# display.net
KiCad netlist of a schematic drawn in Altium Designer
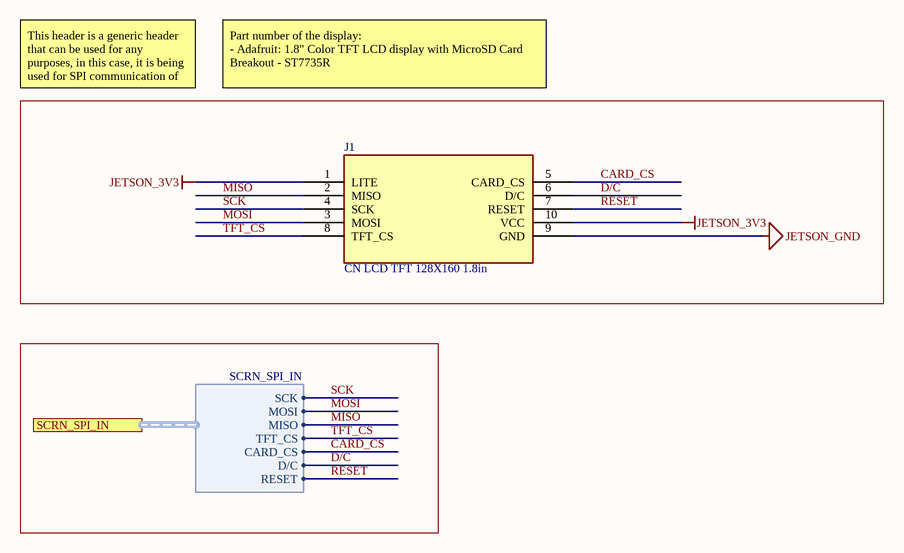
[diagram p0: display.SchDoc]

(export (version "E")
  (design (tool "Eeschema 10.0.6"))
  (components
    (comp (ref "J1")
      (value "CN LCD TFT 128X160 1.8in")
      (footprint "CN LCD TFT 128X160 1.8in")
      (libsource (lib "Connector_Library") (part "CN LCD TFT 128X160 1.8in"))
    )
  )
  (nets
    (net (code "2") (name "/CARD_CS") (class "Default")
      (node (ref "J1") (pin "5") (pinfunction "CARD_CS_5") (pintype "passive"))
    )
    (net (code "3") (name "/D{slash}C") (class "Default")
      (node (ref "J1") (pin "6") (pinfunction "D/C_6") (pintype "passive"))
    )
    (net (code "4") (name "/MISO") (class "Default")
      (node (ref "J1") (pin "2") (pinfunction "MISO_2") (pintype "passive"))
    )
    (net (code "5") (name "/MOSI") (class "Default")
      (node (ref "J1") (pin "3") (pinfunction "MOSI_3") (pintype "passive"))
    )
    (net (code "6") (name "/RESET") (class "Default")
      (node (ref "J1") (pin "7") (pinfunction "RESET_7") (pintype "passive"))
    )
    (net (code "7") (name "/SCK") (class "Default")
      (node (ref "J1") (pin "4") (pinfunction "SCK_4") (pintype "passive"))
    )
    (net (code "8") (name "/TFT_CS") (class "Default")
      (node (ref "J1") (pin "8") (pinfunction "TFT_CS_8") (pintype "passive"))
    )
    (net (code "10") (name "JETSON_3V3") (class "Default")
      (node (ref "J1") (pin "1") (pinfunction "LITE_1") (pintype "passive"))
      (node (ref "J1") (pin "10") (pinfunction "VCC_10") (pintype "passive"))
    )
    (net (code "11") (name "JETSON_GND") (class "Default")
      (node (ref "J1") (pin "9") (pinfunction "GND_9") (pintype "passive"))
    )
  )
)
